# 2_cyber60-smk_matrix.net
KiCad netlist of a schematic drawn in Altium Designer
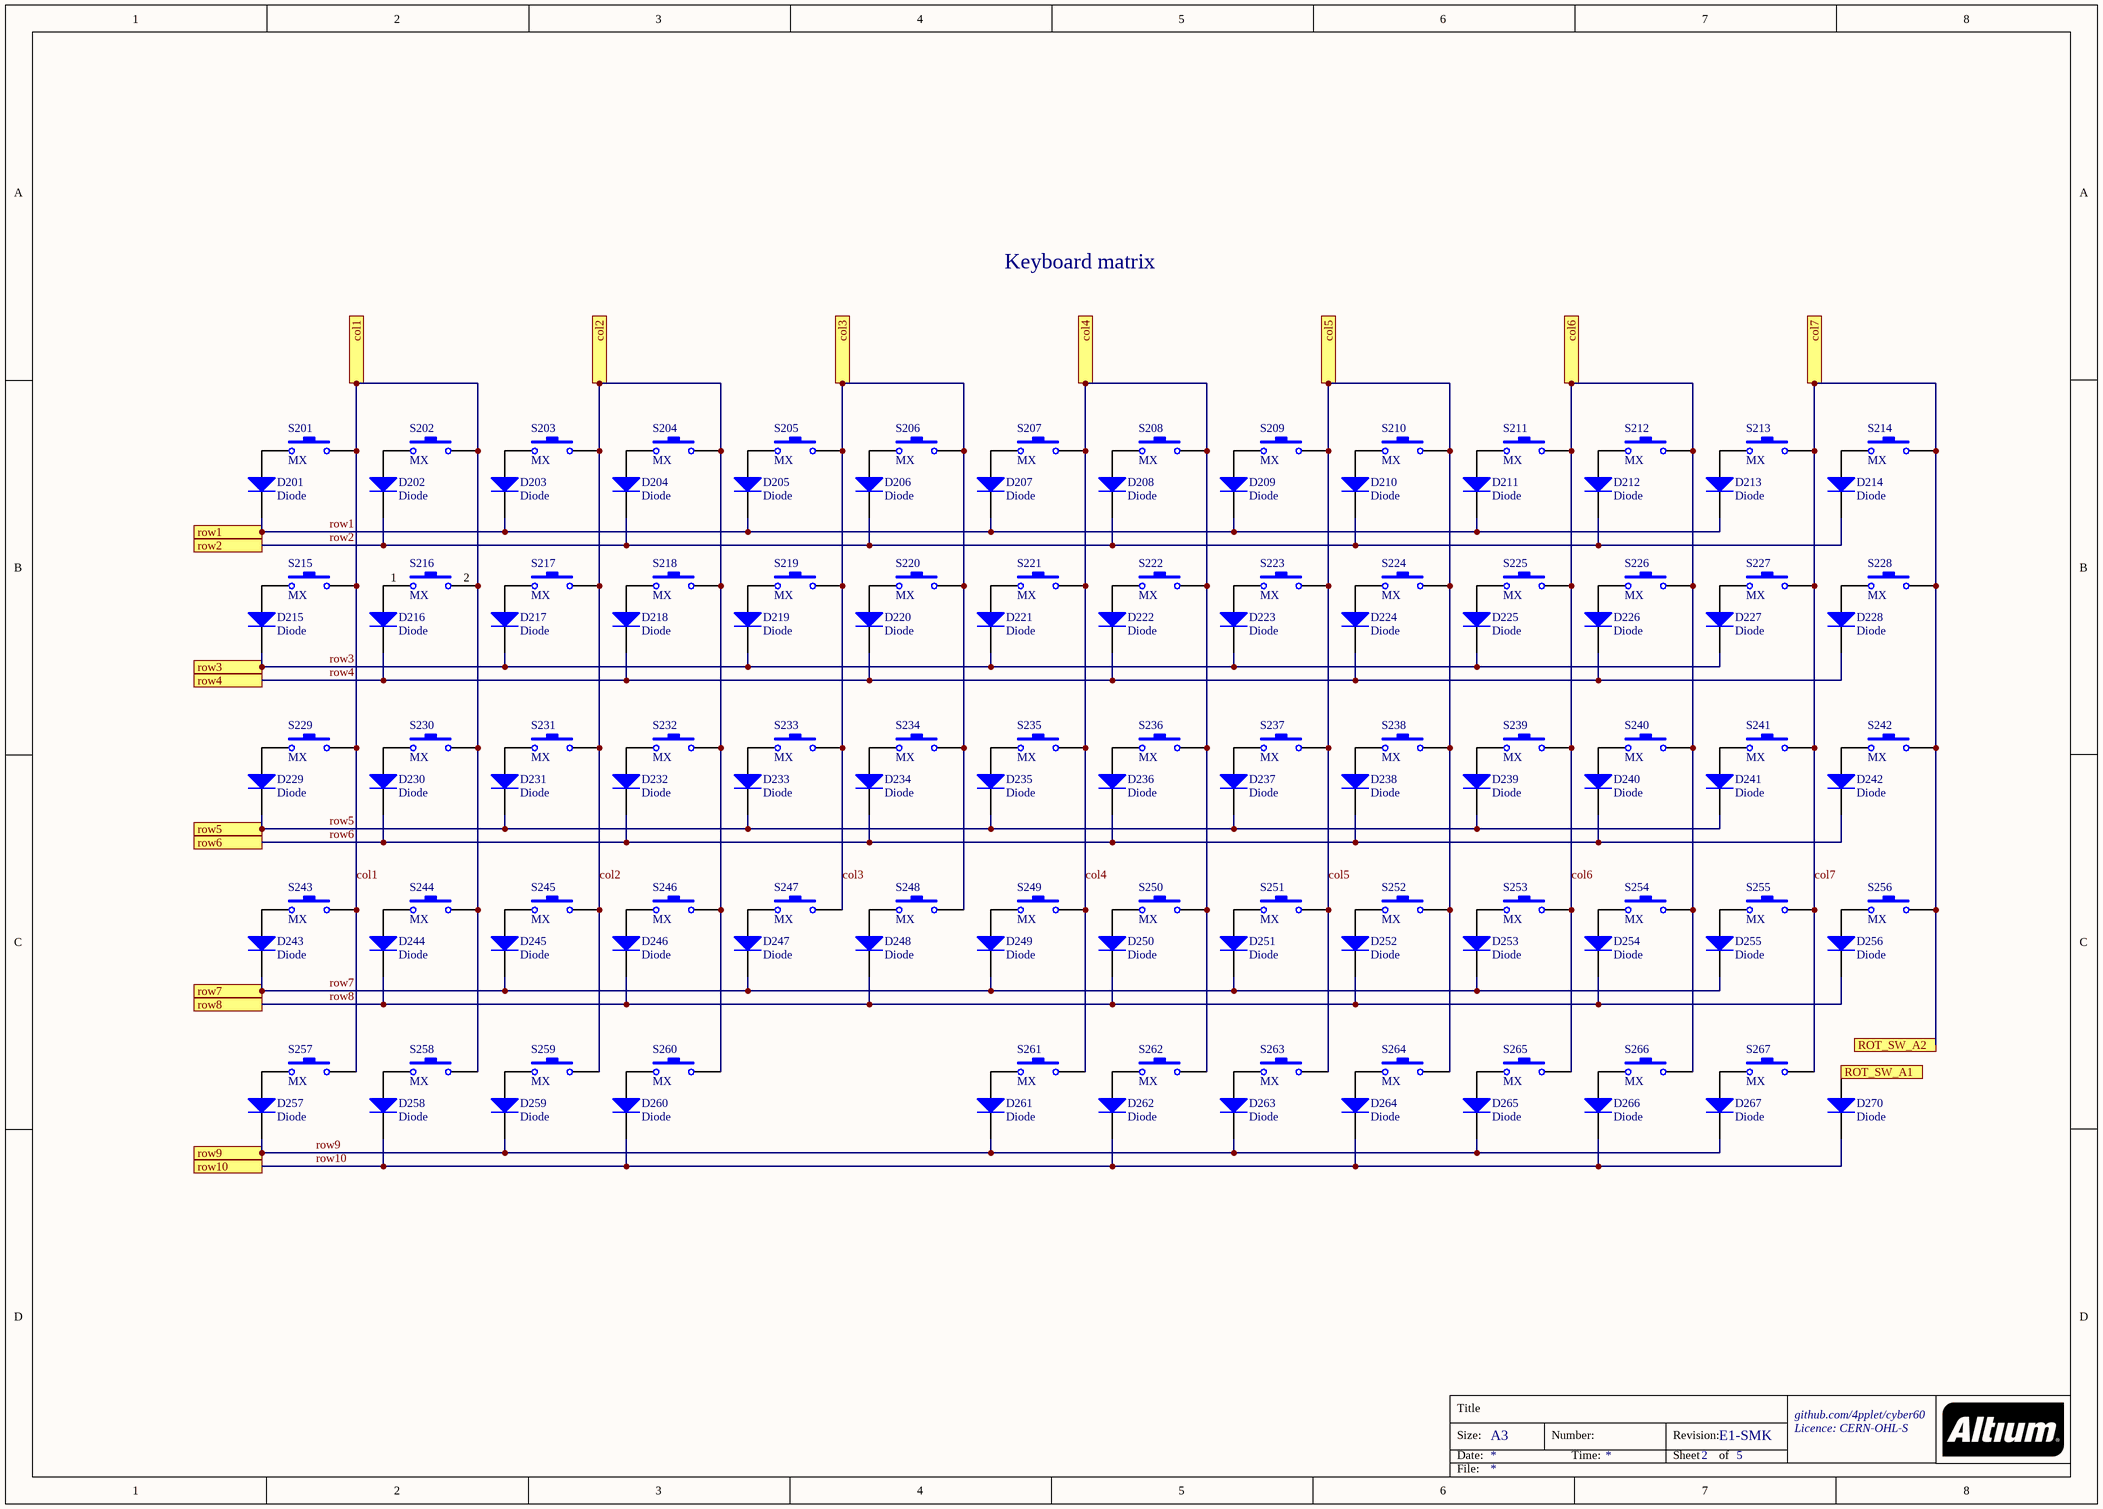
[diagram p0: 2_cyber60-smk_matrix.SchDoc]

(export (version "E")
  (design (tool "Eeschema 10.0.6"))
  (components
    (comp (ref "D201")
      (value "Diode")
      (footprint "SOD-123")
      (description "Default Diode")
      (fields (field (name "LCSC PART #") "C81598") (field (name "MRF.PART") "1N4148W"))
      (libsource (lib "Miscellaneous Devices") (part "Diode"))
    )
    (comp (ref "D202")
      (value "Diode")
      (footprint "SOD-123")
      (description "Default Diode")
      (fields (field (name "LCSC PART #") "C81598") (field (name "MRF.PART") "1N4148W"))
      (libsource (lib "Miscellaneous Devices") (part "Diode"))
    )
    (comp (ref "D203")
      (value "Diode")
      (footprint "SOD-123")
      (description "Default Diode")
      (fields (field (name "LCSC PART #") "C81598") (field (name "MRF.PART") "1N4148W"))
      (libsource (lib "Miscellaneous Devices") (part "Diode"))
    )
    (comp (ref "D204")
      (value "Diode")
      (footprint "SOD-123")
      (description "Default Diode")
      (fields (field (name "LCSC PART #") "C81598") (field (name "MRF.PART") "1N4148W"))
      (libsource (lib "Miscellaneous Devices") (part "Diode"))
    )
    (comp (ref "D205")
      (value "Diode")
      (footprint "SOD-123")
      (description "Default Diode")
      (fields (field (name "LCSC PART #") "C81598") (field (name "MRF.PART") "1N4148W"))
      (libsource (lib "Miscellaneous Devices") (part "Diode"))
    )
    (comp (ref "D206")
      (value "Diode")
      (footprint "SOD-123")
      (description "Default Diode")
      (fields (field (name "LCSC PART #") "C81598") (field (name "MRF.PART") "1N4148W"))
      (libsource (lib "Miscellaneous Devices") (part "Diode"))
    )
    (comp (ref "D207")
      (value "Diode")
      (footprint "SOD-123")
      (description "Default Diode")
      (fields (field (name "LCSC PART #") "C81598") (field (name "MRF.PART") "1N4148W"))
      (libsource (lib "Miscellaneous Devices") (part "Diode"))
    )
    (comp (ref "D208")
      (value "Diode")
      (footprint "SOD-123")
      (description "Default Diode")
      (fields (field (name "LCSC PART #") "C81598") (field (name "MRF.PART") "1N4148W"))
      (libsource (lib "Miscellaneous Devices") (part "Diode"))
    )
    (comp (ref "D209")
      (value "Diode")
      (footprint "SOD-123")
      (description "Default Diode")
      (fields (field (name "LCSC PART #") "C81598") (field (name "MRF.PART") "1N4148W"))
      (libsource (lib "Miscellaneous Devices") (part "Diode"))
    )
    (comp (ref "D210")
      (value "Diode")
      (footprint "SOD-123")
      (description "Default Diode")
      (fields (field (name "LCSC PART #") "C81598") (field (name "MRF.PART") "1N4148W"))
      (libsource (lib "Miscellaneous Devices") (part "Diode"))
    )
    (comp (ref "D211")
      (value "Diode")
      (footprint "SOD-123")
      (description "Default Diode")
      (fields (field (name "LCSC PART #") "C81598") (field (name "MRF.PART") "1N4148W"))
      (libsource (lib "Miscellaneous Devices") (part "Diode"))
    )
    (comp (ref "D212")
      (value "Diode")
      (footprint "SOD-123")
      (description "Default Diode")
      (fields (field (name "LCSC PART #") "C81598") (field (name "MRF.PART") "1N4148W"))
      (libsource (lib "Miscellaneous Devices") (part "Diode"))
    )
    (comp (ref "D213")
      (value "Diode")
      (footprint "SOD-123")
      (description "Default Diode")
      (fields (field (name "LCSC PART #") "C81598") (field (name "MRF.PART") "1N4148W"))
      (libsource (lib "Miscellaneous Devices") (part "Diode"))
    )
    (comp (ref "D214")
      (value "Diode")
      (footprint "SOD-123")
      (description "Default Diode")
      (fields (field (name "LCSC PART #") "C81598") (field (name "MRF.PART") "1N4148W"))
      (libsource (lib "Miscellaneous Devices") (part "Diode"))
    )
    (comp (ref "D215")
      (value "Diode")
      (footprint "SOD-123")
      (description "Default Diode")
      (fields (field (name "LCSC PART #") "C81598") (field (name "MRF.PART") "1N4148W"))
      (libsource (lib "Miscellaneous Devices") (part "Diode"))
    )
    (comp (ref "D216")
      (value "Diode")
      (footprint "SOD-123")
      (description "Default Diode")
      (fields (field (name "LCSC PART #") "C81598") (field (name "MRF.PART") "1N4148W"))
      (libsource (lib "Miscellaneous Devices") (part "Diode"))
    )
    (comp (ref "D217")
      (value "Diode")
      (footprint "SOD-123")
      (description "Default Diode")
      (fields (field (name "LCSC PART #") "C81598") (field (name "MRF.PART") "1N4148W"))
      (libsource (lib "Miscellaneous Devices") (part "Diode"))
    )
    (comp (ref "D218")
      (value "Diode")
      (footprint "SOD-123")
      (description "Default Diode")
      (fields (field (name "LCSC PART #") "C81598") (field (name "MRF.PART") "1N4148W"))
      (libsource (lib "Miscellaneous Devices") (part "Diode"))
    )
    (comp (ref "D219")
      (value "Diode")
      (footprint "SOD-123")
      (description "Default Diode")
      (fields (field (name "LCSC PART #") "C81598") (field (name "MRF.PART") "1N4148W"))
      (libsource (lib "Miscellaneous Devices") (part "Diode"))
    )
    (comp (ref "D220")
      (value "Diode")
      (footprint "SOD-123")
      (description "Default Diode")
      (fields (field (name "LCSC PART #") "C81598") (field (name "MRF.PART") "1N4148W"))
      (libsource (lib "Miscellaneous Devices") (part "Diode"))
    )
    (comp (ref "D221")
      (value "Diode")
      (footprint "SOD-123")
      (description "Default Diode")
      (fields (field (name "LCSC PART #") "C81598") (field (name "MRF.PART") "1N4148W"))
      (libsource (lib "Miscellaneous Devices") (part "Diode"))
    )
    (comp (ref "D222")
      (value "Diode")
      (footprint "SOD-123")
      (description "Default Diode")
      (fields (field (name "LCSC PART #") "C81598") (field (name "MRF.PART") "1N4148W"))
      (libsource (lib "Miscellaneous Devices") (part "Diode"))
    )
    (comp (ref "D223")
      (value "Diode")
      (footprint "SOD-123")
      (description "Default Diode")
      (fields (field (name "LCSC PART #") "C81598") (field (name "MRF.PART") "1N4148W"))
      (libsource (lib "Miscellaneous Devices") (part "Diode"))
    )
    (comp (ref "D224")
      (value "Diode")
      (footprint "SOD-123")
      (description "Default Diode")
      (fields (field (name "LCSC PART #") "C81598") (field (name "MRF.PART") "1N4148W"))
      (libsource (lib "Miscellaneous Devices") (part "Diode"))
    )
    (comp (ref "D225")
      (value "Diode")
      (footprint "SOD-123")
      (description "Default Diode")
      (fields (field (name "LCSC PART #") "C81598") (field (name "MRF.PART") "1N4148W"))
      (libsource (lib "Miscellaneous Devices") (part "Diode"))
    )
    (comp (ref "D226")
      (value "Diode")
      (footprint "SOD-123")
      (description "Default Diode")
      (fields (field (name "LCSC PART #") "C81598") (field (name "MRF.PART") "1N4148W"))
      (libsource (lib "Miscellaneous Devices") (part "Diode"))
    )
    (comp (ref "D227")
      (value "Diode")
      (footprint "SOD-123")
      (description "Default Diode")
      (fields (field (name "LCSC PART #") "C81598") (field (name "MRF.PART") "1N4148W"))
      (libsource (lib "Miscellaneous Devices") (part "Diode"))
    )
    (comp (ref "D228")
      (value "Diode")
      (footprint "SOD-123")
      (description "Default Diode")
      (fields (field (name "LCSC PART #") "C81598") (field (name "MRF.PART") "1N4148W"))
      (libsource (lib "Miscellaneous Devices") (part "Diode"))
    )
    (comp (ref "D229")
      (value "Diode")
      (footprint "SOD-123")
      (description "Default Diode")
      (fields (field (name "LCSC PART #") "C81598") (field (name "MRF.PART") "1N4148W"))
      (libsource (lib "Miscellaneous Devices") (part "Diode"))
    )
    (comp (ref "D230")
      (value "Diode")
      (footprint "SOD-123")
      (description "Default Diode")
      (fields (field (name "LCSC PART #") "C81598") (field (name "MRF.PART") "1N4148W"))
      (libsource (lib "Miscellaneous Devices") (part "Diode"))
    )
    (comp (ref "D231")
      (value "Diode")
      (footprint "SOD-123")
      (description "Default Diode")
      (fields (field (name "LCSC PART #") "C81598") (field (name "MRF.PART") "1N4148W"))
      (libsource (lib "Miscellaneous Devices") (part "Diode"))
    )
    (comp (ref "D232")
      (value "Diode")
      (footprint "SOD-123")
      (description "Default Diode")
      (fields (field (name "LCSC PART #") "C81598") (field (name "MRF.PART") "1N4148W"))
      (libsource (lib "Miscellaneous Devices") (part "Diode"))
    )
    (comp (ref "D233")
      (value "Diode")
      (footprint "SOD-123")
      (description "Default Diode")
      (fields (field (name "LCSC PART #") "C81598") (field (name "MRF.PART") "1N4148W"))
      (libsource (lib "Miscellaneous Devices") (part "Diode"))
    )
    (comp (ref "D234")
      (value "Diode")
      (footprint "SOD-123")
      (description "Default Diode")
      (fields (field (name "LCSC PART #") "C81598") (field (name "MRF.PART") "1N4148W"))
      (libsource (lib "Miscellaneous Devices") (part "Diode"))
    )
    (comp (ref "D235")
      (value "Diode")
      (footprint "SOD-123")
      (description "Default Diode")
      (fields (field (name "LCSC PART #") "C81598") (field (name "MRF.PART") "1N4148W"))
      (libsource (lib "Miscellaneous Devices") (part "Diode"))
    )
    (comp (ref "D236")
      (value "Diode")
      (footprint "SOD-123")
      (description "Default Diode")
      (fields (field (name "LCSC PART #") "C81598") (field (name "MRF.PART") "1N4148W"))
      (libsource (lib "Miscellaneous Devices") (part "Diode"))
    )
    (comp (ref "D237")
      (value "Diode")
      (footprint "SOD-123")
      (description "Default Diode")
      (fields (field (name "LCSC PART #") "C81598") (field (name "MRF.PART") "1N4148W"))
      (libsource (lib "Miscellaneous Devices") (part "Diode"))
    )
    (comp (ref "D238")
      (value "Diode")
      (footprint "SOD-123")
      (description "Default Diode")
      (fields (field (name "LCSC PART #") "C81598") (field (name "MRF.PART") "1N4148W"))
      (libsource (lib "Miscellaneous Devices") (part "Diode"))
    )
    (comp (ref "D239")
      (value "Diode")
      (footprint "SOD-123")
      (description "Default Diode")
      (fields (field (name "LCSC PART #") "C81598") (field (name "MRF.PART") "1N4148W"))
      (libsource (lib "Miscellaneous Devices") (part "Diode"))
    )
    (comp (ref "D240")
      (value "Diode")
      (footprint "SOD-123")
      (description "Default Diode")
      (fields (field (name "LCSC PART #") "C81598") (field (name "MRF.PART") "1N4148W"))
      (libsource (lib "Miscellaneous Devices") (part "Diode"))
    )
    (comp (ref "D241")
      (value "Diode")
      (footprint "SOD-123")
      (description "Default Diode")
      (fields (field (name "LCSC PART #") "C81598") (field (name "MRF.PART") "1N4148W"))
      (libsource (lib "Miscellaneous Devices") (part "Diode"))
    )
    (comp (ref "D242")
      (value "Diode")
      (footprint "SOD-123")
      (description "Default Diode")
      (fields (field (name "LCSC PART #") "C81598") (field (name "MRF.PART") "1N4148W"))
      (libsource (lib "Miscellaneous Devices") (part "Diode"))
    )
    (comp (ref "D243")
      (value "Diode")
      (footprint "SOD-123")
      (description "Default Diode")
      (fields (field (name "LCSC PART #") "C81598") (field (name "MRF.PART") "1N4148W"))
      (libsource (lib "Miscellaneous Devices") (part "Diode"))
    )
    (comp (ref "D244")
      (value "Diode")
      (footprint "SOD-123")
      (description "Default Diode")
      (fields (field (name "LCSC PART #") "C81598") (field (name "MRF.PART") "1N4148W"))
      (libsource (lib "Miscellaneous Devices") (part "Diode"))
    )
    (comp (ref "D245")
      (value "Diode")
      (footprint "SOD-123")
      (description "Default Diode")
      (fields (field (name "LCSC PART #") "C81598") (field (name "MRF.PART") "1N4148W"))
      (libsource (lib "Miscellaneous Devices") (part "Diode"))
    )
    (comp (ref "D246")
      (value "Diode")
      (footprint "SOD-123")
      (description "Default Diode")
      (fields (field (name "LCSC PART #") "C81598") (field (name "MRF.PART") "1N4148W"))
      (libsource (lib "Miscellaneous Devices") (part "Diode"))
    )
    (comp (ref "D247")
      (value "Diode")
      (footprint "SOD-123")
      (description "Default Diode")
      (fields (field (name "LCSC PART #") "C81598") (field (name "MRF.PART") "1N4148W"))
      (libsource (lib "Miscellaneous Devices") (part "Diode"))
    )
    (comp (ref "D248")
      (value "Diode")
      (footprint "SOD-123")
      (description "Default Diode")
      (fields (field (name "LCSC PART #") "C81598") (field (name "MRF.PART") "1N4148W"))
      (libsource (lib "Miscellaneous Devices") (part "Diode"))
    )
    (comp (ref "D249")
      (value "Diode")
      (footprint "SOD-123")
      (description "Default Diode")
      (fields (field (name "LCSC PART #") "C81598") (field (name "MRF.PART") "1N4148W"))
      (libsource (lib "Miscellaneous Devices") (part "Diode"))
    )
    (comp (ref "D250")
      (value "Diode")
      (footprint "SOD-123")
      (description "Default Diode")
      (fields (field (name "LCSC PART #") "C81598") (field (name "MRF.PART") "1N4148W"))
      (libsource (lib "Miscellaneous Devices") (part "Diode"))
    )
    (comp (ref "D251")
      (value "Diode")
      (footprint "SOD-123")
      (description "Default Diode")
      (fields (field (name "LCSC PART #") "C81598") (field (name "MRF.PART") "1N4148W"))
      (libsource (lib "Miscellaneous Devices") (part "Diode"))
    )
    (comp (ref "D252")
      (value "Diode")
      (footprint "SOD-123")
      (description "Default Diode")
      (fields (field (name "LCSC PART #") "C81598") (field (name "MRF.PART") "1N4148W"))
      (libsource (lib "Miscellaneous Devices") (part "Diode"))
    )
    (comp (ref "D253")
      (value "Diode")
      (footprint "SOD-123")
      (description "Default Diode")
      (fields (field (name "LCSC PART #") "C81598") (field (name "MRF.PART") "1N4148W"))
      (libsource (lib "Miscellaneous Devices") (part "Diode"))
    )
    (comp (ref "D254")
      (value "Diode")
      (footprint "SOD-123")
      (description "Default Diode")
      (fields (field (name "LCSC PART #") "C81598") (field (name "MRF.PART") "1N4148W"))
      (libsource (lib "Miscellaneous Devices") (part "Diode"))
    )
    (comp (ref "D255")
      (value "Diode")
      (footprint "SOD-123")
      (description "Default Diode")
      (fields (field (name "LCSC PART #") "C81598") (field (name "MRF.PART") "1N4148W"))
      (libsource (lib "Miscellaneous Devices") (part "Diode"))
    )
    (comp (ref "D256")
      (value "Diode")
      (footprint "SOD-123")
      (description "Default Diode")
      (fields (field (name "LCSC PART #") "C81598") (field (name "MRF.PART") "1N4148W"))
      (libsource (lib "Miscellaneous Devices") (part "Diode"))
    )
    (comp (ref "D257")
      (value "Diode")
      (footprint "SOD-123")
      (description "Default Diode")
      (fields (field (name "LCSC PART #") "C81598") (field (name "MRF.PART") "1N4148W"))
      (libsource (lib "Miscellaneous Devices") (part "Diode"))
    )
    (comp (ref "D258")
      (value "Diode")
      (footprint "SOD-123")
      (description "Default Diode")
      (fields (field (name "LCSC PART #") "C81598") (field (name "MRF.PART") "1N4148W"))
      (libsource (lib "Miscellaneous Devices") (part "Diode"))
    )
    (comp (ref "D259")
      (value "Diode")
      (footprint "SOD-123")
      (description "Default Diode")
      (fields (field (name "LCSC PART #") "C81598") (field (name "MRF.PART") "1N4148W"))
      (libsource (lib "Miscellaneous Devices") (part "Diode"))
    )
    (comp (ref "D260")
      (value "Diode")
      (footprint "SOD-123")
      (description "Default Diode")
      (fields (field (name "LCSC PART #") "C81598") (field (name "MRF.PART") "1N4148W"))
      (libsource (lib "Miscellaneous Devices") (part "Diode"))
    )
    (comp (ref "D261")
      (value "Diode")
      (footprint "SOD-123")
      (description "Default Diode")
      (fields (field (name "LCSC PART #") "C81598") (field (name "MRF.PART") "1N4148W"))
      (libsource (lib "Miscellaneous Devices") (part "Diode"))
    )
    (comp (ref "D262")
      (value "Diode")
      (footprint "SOD-123")
      (description "Default Diode")
      (fields (field (name "LCSC PART #") "C81598") (field (name "MRF.PART") "1N4148W"))
      (libsource (lib "Miscellaneous Devices") (part "Diode"))
    )
    (comp (ref "D263")
      (value "Diode")
      (footprint "SOD-123")
      (description "Default Diode")
      (fields (field (name "LCSC PART #") "C81598") (field (name "MRF.PART") "1N4148W"))
      (libsource (lib "Miscellaneous Devices") (part "Diode"))
    )
    (comp (ref "D264")
      (value "Diode")
      (footprint "SOD-123")
      (description "Default Diode")
      (fields (field (name "LCSC PART #") "C81598") (field (name "MRF.PART") "1N4148W"))
      (libsource (lib "Miscellaneous Devices") (part "Diode"))
    )
    (comp (ref "D265")
      (value "Diode")
      (footprint "SOD-123")
      (description "Default Diode")
      (fields (field (name "LCSC PART #") "C81598") (field (name "MRF.PART") "1N4148W"))
      (libsource (lib "Miscellaneous Devices") (part "Diode"))
    )
    (comp (ref "D266")
      (value "Diode")
      (footprint "SOD-123")
      (description "Default Diode")
      (fields (field (name "LCSC PART #") "C81598") (field (name "MRF.PART") "1N4148W"))
      (libsource (lib "Miscellaneous Devices") (part "Diode"))
    )
    (comp (ref "D267")
      (value "Diode")
      (footprint "SOD-123")
      (description "Default Diode")
      (fields (field (name "LCSC PART #") "C81598") (field (name "MRF.PART") "1N4148W"))
      (libsource (lib "Miscellaneous Devices") (part "Diode"))
    )
    (comp (ref "D270")
      (value "Diode")
      (footprint "SOD-123")
      (description "Default Diode")
      (fields (field (name "LCSC PART #") "C81598") (field (name "MRF.PART") "1N4148W"))
      (libsource (lib "Miscellaneous Devices") (part "Diode"))
    )
    (comp (ref "S201")
      (value "MX")
      (footprint "SMK-switch")
      (description "Switch")
      (libsource (lib "Miscellaneous Devices") (part "SW-PB"))
    )
    (comp (ref "S202")
      (value "MX")
      (footprint "SMK-switch - switched polarity")
      (description "Switch")
      (libsource (lib "Miscellaneous Devices") (part "SW-PB"))
    )
    (comp (ref "S203")
      (value "MX")
      (footprint "SMK-switch - switched polarity")
      (description "Switch")
      (libsource (lib "Miscellaneous Devices") (part "SW-PB"))
    )
    (comp (ref "S204")
      (value "MX")
      (footprint "SMK-switch")
      (description "Switch")
      (libsource (lib "Miscellaneous Devices") (part "SW-PB"))
    )
    (comp (ref "S205")
      (value "MX")
      (footprint "SMK-switch - switched polarity")
      (description "Switch")
      (libsource (lib "Miscellaneous Devices") (part "SW-PB"))
    )
    (comp (ref "S206")
      (value "MX")
      (footprint "SMK-switch - switched polarity")
      (description "Switch")
      (libsource (lib "Miscellaneous Devices") (part "SW-PB"))
    )
    (comp (ref "S207")
      (value "MX")
      (footprint "SMK-switch - switched polarity")
      (description "Switch")
      (libsource (lib "Miscellaneous Devices") (part "SW-PB"))
    )
    (comp (ref "S208")
      (value "MX")
      (footprint "SMK-switch - switched polarity")
      (description "Switch")
      (libsource (lib "Miscellaneous Devices") (part "SW-PB"))
    )
    (comp (ref "S209")
      (value "MX")
      (footprint "SMK-switch - switched polarity")
      (description "Switch")
      (libsource (lib "Miscellaneous Devices") (part "SW-PB"))
    )
    (comp (ref "S210")
      (value "MX")
      (footprint "SMK-switch - switched polarity")
      (description "Switch")
      (libsource (lib "Miscellaneous Devices") (part "SW-PB"))
    )
    (comp (ref "S211")
      (value "MX")
      (footprint "SMK-switch - switched polarity")
      (description "Switch")
      (libsource (lib "Miscellaneous Devices") (part "SW-PB"))
    )
    (comp (ref "S212")
      (value "MX")
      (footprint "SMK-switch - switched polarity")
      (description "Switch")
      (libsource (lib "Miscellaneous Devices") (part "SW-PB"))
    )
    (comp (ref "S213")
      (value "MX")
      (footprint "SMK-switch - switched polarity")
      (description "Switch")
      (libsource (lib "Miscellaneous Devices") (part "SW-PB"))
    )
    (comp (ref "S214")
      (value "MX")
      (footprint "SMK-switch - switched polarity")
      (description "Switch")
      (libsource (lib "Miscellaneous Devices") (part "SW-PB"))
    )
    (comp (ref "S215")
      (value "MX")
      (footprint "SMK-switch - switched polarity")
      (description "TAB")
      (libsource (lib "Miscellaneous Devices") (part "SW-PB"))
    )
    (comp (ref "S216")
      (value "MX")
      (footprint "SMK-switch - switched polarity")
      (description "Switch")
      (libsource (lib "") (part "SW-PB_1"))
    )
    (comp (ref "S217")
      (value "MX")
      (footprint "SMK-switch - switched polarity")
      (description "Switch")
      (libsource (lib "Miscellaneous Devices") (part "SW-PB"))
    )
    (comp (ref "S218")
      (value "MX")
      (footprint "SMK-switch - switched polarity")
      (description "Switch")
      (libsource (lib "Miscellaneous Devices") (part "SW-PB"))
    )
    (comp (ref "S219")
      (value "MX")
      (footprint "SMK-switch - switched polarity")
      (description "Switch")
      (libsource (lib "Miscellaneous Devices") (part "SW-PB"))
    )
    (comp (ref "S220")
      (value "MX")
      (footprint "SMK-switch")
      (description "Switch")
      (libsource (lib "Miscellaneous Devices") (part "SW-PB"))
    )
    (comp (ref "S221")
      (value "MX")
      (footprint "SMK-switch - switched polarity")
      (description "Switch")
      (libsource (lib "Miscellaneous Devices") (part "SW-PB"))
    )
    (comp (ref "S222")
      (value "MX")
      (footprint "SMK-switch - switched polarity")
      (description "Switch")
      (libsource (lib "Miscellaneous Devices") (part "SW-PB"))
    )
    (comp (ref "S223")
      (value "MX")
      (footprint "SMK-switch - switched polarity")
      (description "Switch")
      (libsource (lib "Miscellaneous Devices") (part "SW-PB"))
    )
    (comp (ref "S224")
      (value "MX")
      (footprint "SMK-switch - switched polarity")
      (description "Switch")
      (libsource (lib "Miscellaneous Devices") (part "SW-PB"))
    )
    (comp (ref "S225")
      (value "MX")
      (footprint "SMK-switch - switched polarity")
      (description "Switch")
      (libsource (lib "Miscellaneous Devices") (part "SW-PB"))
    )
    (comp (ref "S226")
      (value "MX")
      (footprint "SMK-switch")
      (description "Switch")
      (libsource (lib "Miscellaneous Devices") (part "SW-PB"))
    )
    (comp (ref "S227")
      (value "MX")
      (footprint "SMK-switch")
      (description "Switch")
      (libsource (lib "Miscellaneous Devices") (part "SW-PB"))
    )
    (comp (ref "S228")
      (value "MX")
      (footprint "SMK-switch - backspace")
      (description "Switch")
      (libsource (lib "Miscellaneous Devices") (part "SW-PB"))
    )
    (comp (ref "S229")
      (value "MX")
      (footprint "SMK-switch - CAPS")
      (description "Switch")
      (libsource (lib "Miscellaneous Devices") (part "SW-PB"))
    )
    (comp (ref "S230")
      (value "MX")
      (footprint "SMK-switch - switched polarity")
      (description "Switch")
      (libsource (lib "Miscellaneous Devices") (part "SW-PB"))
    )
    (comp (ref "S231")
      (value "MX")
      (footprint "SMK-switch - switched polarity")
      (description "Switch")
      (libsource (lib "Miscellaneous Devices") (part "SW-PB"))
    )
    (comp (ref "S232")
      (value "MX")
      (footprint "SMK-switch - switched polarity")
      (description "Switch")
      (libsource (lib "Miscellaneous Devices") (part "SW-PB"))
    )
    (comp (ref "S233")
      (value "MX")
      (footprint "SMK-switch - switched polarity")
      (description "Switch")
      (libsource (lib "Miscellaneous Devices") (part "SW-PB"))
    )
    (comp (ref "S234")
      (value "MX")
      (footprint "SMK-switch")
      (description "Switch")
      (libsource (lib "Miscellaneous Devices") (part "SW-PB"))
    )
    (comp (ref "S235")
      (value "MX")
      (footprint "SMK-switch - switched polarity")
      (description "Switch")
      (libsource (lib "Miscellaneous Devices") (part "SW-PB"))
    )
    (comp (ref "S236")
      (value "MX")
      (footprint "SMK-switch - switched polarity")
      (description "Switch")
      (libsource (lib "Miscellaneous Devices") (part "SW-PB"))
    )
    (comp (ref "S237")
      (value "MX")
      (footprint "SMK-switch - switched polarity")
      (description "Switch")
      (libsource (lib "Miscellaneous Devices") (part "SW-PB"))
    )
    (comp (ref "S238")
      (value "MX")
      (footprint "SMK-switch - switched polarity")
      (description "Switch")
      (libsource (lib "Miscellaneous Devices") (part "SW-PB"))
    )
    (comp (ref "S239")
      (value "MX")
      (footprint "SMK-switch")
      (description "Switch")
      (libsource (lib "Miscellaneous Devices") (part "SW-PB"))
    )
    (comp (ref "S240")
      (value "MX")
      (footprint "SMK-switch - switched polarity")
      (description "Switch")
      (libsource (lib "Miscellaneous Devices") (part "SW-PB"))
    )
    (comp (ref "S241")
      (value "MX")
      (footprint "SMK-switch")
      (description "Switch")
      (libsource (lib "Miscellaneous Devices") (part "SW-PB"))
    )
    (comp (ref "S242")
      (value "MX")
      (footprint "SMK-switch - 1.5U")
      (description "Switch")
      (libsource (lib "Miscellaneous Devices") (part "SW-PB"))
    )
    (comp (ref "S243")
      (value "MX")
      (footprint "SMK-switch - Left shift v2")
      (description "Switch")
      (libsource (lib "Miscellaneous Devices") (part "SW-PB"))
    )
    (comp (ref "S244")
      (value "MX")
      (footprint "SMK-switch - switched polarity")
      (description "Switch")
      (libsource (lib "Miscellaneous Devices") (part "SW-PB"))
    )
    (comp (ref "S245")
      (value "MX")
      (footprint "SMK-switch - switched polarity")
      (description "Switch")
      (libsource (lib "Miscellaneous Devices") (part "SW-PB"))
    )
    (comp (ref "S246")
      (value "MX")
      (footprint "SMK-switch - switched polarity")
      (description "Switch")
      (libsource (lib "Miscellaneous Devices") (part "SW-PB"))
    )
    (comp (ref "S247")
      (value "MX")
      (footprint "SMK-switch - switched polarity")
      (description "Switch")
      (libsource (lib "Miscellaneous Devices") (part "SW-PB"))
    )
    (comp (ref "S248")
      (value "MX")
      (footprint "SMK-switch")
      (description "Switch")
      (libsource (lib "Miscellaneous Devices") (part "SW-PB"))
    )
    (comp (ref "S249")
      (value "MX")
      (footprint "SMK-switch - switched polarity")
      (description "Switch")
      (libsource (lib "Miscellaneous Devices") (part "SW-PB"))
    )
    (comp (ref "S250")
      (value "MX")
      (footprint "SMK-switch")
      (description "Switch")
      (libsource (lib "Miscellaneous Devices") (part "SW-PB"))
    )
    (comp (ref "S251")
      (value "MX")
      (footprint "SMK-switch - switched polarity")
      (description "Switch")
      (libsource (lib "Miscellaneous Devices") (part "SW-PB"))
    )
    (comp (ref "S252")
      (value "MX")
      (footprint "SMK-switch - switched polarity")
      (description "Switch")
      (libsource (lib "Miscellaneous Devices") (part "SW-PB"))
    )
    (comp (ref "S253")
      (value "MX")
      (footprint "SMK-switch - switched polarity")
      (description "Switch")
      (libsource (lib "Miscellaneous Devices") (part "SW-PB"))
    )
    (comp (ref "S254")
      (value "MX")
      (footprint "SMK-switch - switched polarity")
      (description "Switch")
      (libsource (lib "Miscellaneous Devices") (part "SW-PB"))
    )
    (comp (ref "S255")
      (value "MX")
      (footprint "SMK-switch")
      (description "Switch")
      (libsource (lib "Miscellaneous Devices") (part "SW-PB"))
    )
    (comp (ref "S256")
      (value "MX")
      (footprint "SMK-switch - Enter - rotated stab")
      (description "Switch")
      (libsource (lib "Miscellaneous Devices") (part "SW-PB"))
    )
    (comp (ref "S257")
      (value "MX")
      (footprint "SMK-switch - 1.5u MOD-L")
      (description "Switch")
      (libsource (lib "Miscellaneous Devices") (part "SW-PB"))
    )
    (comp (ref "S258")
      (value "MX")
      (footprint "SMK-switch - L_WIN V2")
      (description "Switch")
      (libsource (lib "Miscellaneous Devices") (part "SW-PB"))
    )
    (comp (ref "S259")
      (value "MX")
      (footprint "SMK-switch - L_ALT V2")
      (description "Switch")
      (libsource (lib "Miscellaneous Devices") (part "SW-PB"))
    )
    (comp (ref "S260")
      (value "MX")
      (footprint "SMK-switch - 2.75U - rotated stab")
      (description "Switch")
      (libsource (lib "Miscellaneous Devices") (part "SW-PB"))
    )
    (comp (ref "S261")
      (value "MX")
      (footprint "SMK-switch - Space_V2")
      (description "Switch")
      (libsource (lib "Miscellaneous Devices") (part "SW-PB"))
    )
    (comp (ref "S262")
      (value "MX")
      (footprint "SMK-switch - 2.75U - rotated stab")
      (description "Switch")
      (libsource (lib "Miscellaneous Devices") (part "SW-PB"))
    )
    (comp (ref "S263")
      (value "MX")
      (footprint "SMK-switch - switched polarity")
      (description "Switch")
      (libsource (lib "Miscellaneous Devices") (part "SW-PB"))
    )
    (comp (ref "S264")
      (value "MX")
      (footprint "SMK-switch - R_ALT V2")
      (description "Switch")
      (libsource (lib "Miscellaneous Devices") (part "SW-PB"))
    )
    (comp (ref "S265")
      (value "MX")
      (footprint "SMK-switch - R_WIN V2")
      (description "Switch")
      (libsource (lib "Miscellaneous Devices") (part "SW-PB"))
    )
    (comp (ref "S266")
      (value "MX")
      (footprint "SMK-switch - 1.5u MOD-R")
      (description "Switch")
      (libsource (lib "Miscellaneous Devices") (part "SW-PB"))
    )
    (comp (ref "S267")
      (value "MX")
      (footprint "SMK-switch - right shift v2")
      (description "Switch")
      (libsource (lib "Miscellaneous Devices") (part "SW-PB"))
    )
  )
  (nets
    (net (code "1") (name "/ROT_SW_A1") (class "Default")
      (node (ref "D270") (pin "1") (pinfunction "A_1") (pintype "passive"))
    )
    (net (code "2") (name "/col1") (class "Default")
      (node (ref "S201") (pin "2") (pinfunction "2_2") (pintype "passive"))
      (node (ref "S202") (pin "2") (pinfunction "2_2") (pintype "passive"))
      (node (ref "S215") (pin "2") (pinfunction "2_2") (pintype "passive"))
      (node (ref "S216") (pin "2") (pinfunction "2_2") (pintype "passive"))
      (node (ref "S229") (pin "2") (pinfunction "2_2") (pintype "passive"))
      (node (ref "S230") (pin "2") (pinfunction "2_2") (pintype "passive"))
      (node (ref "S243") (pin "2") (pinfunction "2_2") (pintype "passive"))
      (node (ref "S244") (pin "2") (pinfunction "2_2") (pintype "passive"))
      (node (ref "S257") (pin "2") (pinfunction "2_2") (pintype "passive"))
      (node (ref "S258") (pin "2") (pinfunction "2_2") (pintype "passive"))
    )
    (net (code "3") (name "/col2") (class "Default")
      (node (ref "S203") (pin "2") (pinfunction "2_2") (pintype "passive"))
      (node (ref "S204") (pin "2") (pinfunction "2_2") (pintype "passive"))
      (node (ref "S217") (pin "2") (pinfunction "2_2") (pintype "passive"))
      (node (ref "S218") (pin "2") (pinfunction "2_2") (pintype "passive"))
      (node (ref "S231") (pin "2") (pinfunction "2_2") (pintype "passive"))
      (node (ref "S232") (pin "2") (pinfunction "2_2") (pintype "passive"))
      (node (ref "S245") (pin "2") (pinfunction "2_2") (pintype "passive"))
      (node (ref "S246") (pin "2") (pinfunction "2_2") (pintype "passive"))
      (node (ref "S259") (pin "2") (pinfunction "2_2") (pintype "passive"))
      (node (ref "S260") (pin "2") (pinfunction "2_2") (pintype "passive"))
    )
    (net (code "4") (name "/col3") (class "Default")
      (node (ref "S205") (pin "2") (pinfunction "2_2") (pintype "passive"))
      (node (ref "S206") (pin "2") (pinfunction "2_2") (pintype "passive"))
      (node (ref "S219") (pin "2") (pinfunction "2_2") (pintype "passive"))
      (node (ref "S220") (pin "2") (pinfunction "2_2") (pintype "passive"))
      (node (ref "S233") (pin "2") (pinfunction "2_2") (pintype "passive"))
      (node (ref "S234") (pin "2") (pinfunction "2_2") (pintype "passive"))
      (node (ref "S247") (pin "2") (pinfunction "2_2") (pintype "passive"))
      (node (ref "S248") (pin "2") (pinfunction "2_2") (pintype "passive"))
    )
    (net (code "5") (name "/col4") (class "Default")
      (node (ref "S207") (pin "2") (pinfunction "2_2") (pintype "passive"))
      (node (ref "S208") (pin "2") (pinfunction "2_2") (pintype "passive"))
      (node (ref "S221") (pin "2") (pinfunction "2_2") (pintype "passive"))
      (node (ref "S222") (pin "2") (pinfunction "2_2") (pintype "passive"))
      (node (ref "S235") (pin "2") (pinfunction "2_2") (pintype "passive"))
      (node (ref "S236") (pin "2") (pinfunction "2_2") (pintype "passive"))
      (node (ref "S249") (pin "2") (pinfunction "2_2") (pintype "passive"))
      (node (ref "S250") (pin "2") (pinfunction "2_2") (pintype "passive"))
      (node (ref "S261") (pin "1") (pinfunction "1_1") (pintype "passive"))
      (node (ref "S262") (pin "2") (pinfunction "2_2") (pintype "passive"))
    )
    (net (code "6") (name "/col5") (class "Default")
      (node (ref "S209") (pin "2") (pinfunction "2_2") (pintype "passive"))
      (node (ref "S210") (pin "2") (pinfunction "2_2") (pintype "passive"))
      (node (ref "S223") (pin "2") (pinfunction "2_2") (pintype "passive"))
      (node (ref "S224") (pin "2") (pinfunction "2_2") (pintype "passive"))
      (node (ref "S237") (pin "2") (pinfunction "2_2") (pintype "passive"))
      (node (ref "S238") (pin "2") (pinfunction "2_2") (pintype "passive"))
      (node (ref "S251") (pin "2") (pinfunction "2_2") (pintype "passive"))
      (node (ref "S252") (pin "2") (pinfunction "2_2") (pintype "passive"))
      (node (ref "S263") (pin "2") (pinfunction "2_2") (pintype "passive"))
      (node (ref "S264") (pin "1") (pinfunction "1_1") (pintype "passive"))
    )
    (net (code "7") (name "/col6") (class "Default")
      (node (ref "S211") (pin "2") (pinfunction "2_2") (pintype "passive"))
      (node (ref "S212") (pin "2") (pinfunction "2_2") (pintype "passive"))
      (node (ref "S225") (pin "2") (pinfunction "2_2") (pintype "passive"))
      (node (ref "S226") (pin "2") (pinfunction "2_2") (pintype "passive"))
      (node (ref "S239") (pin "2") (pinfunction "2_2") (pintype "passive"))
      (node (ref "S240") (pin "2") (pinfunction "2_2") (pintype "passive"))
      (node (ref "S253") (pin "2") (pinfunction "2_2") (pintype "passive"))
      (node (ref "S254") (pin "2") (pinfunction "2_2") (pintype "passive"))
      (node (ref "S265") (pin "2") (pinfunction "2_2") (pintype "passive"))
      (node (ref "S266") (pin "2") (pinfunction "2_2") (pintype "passive"))
    )
    (net (code "8") (name "/col7") (class "Default")
      (node (ref "S213") (pin "2") (pinfunction "2_2") (pintype "passive"))
      (node (ref "S214") (pin "2") (pinfunction "2_2") (pintype "passive"))
      (node (ref "S227") (pin "2") (pinfunction "2_2") (pintype "passive"))
      (node (ref "S228") (pin "1") (pinfunction "1_1") (pintype "passive"))
      (node (ref "S241") (pin "2") (pinfunction "2_2") (pintype "passive"))
      (node (ref "S242") (pin "2") (pinfunction "2_2") (pintype "passive"))
      (node (ref "S255") (pin "2") (pinfunction "2_2") (pintype "passive"))
      (node (ref "S256") (pin "2") (pinfunction "2_2") (pintype "passive"))
      (node (ref "S267") (pin "2") (pinfunction "2_2") (pintype "passive"))
    )
    (net (code "9") (name "/row1") (class "Default")
      (node (ref "D201") (pin "2") (pinfunction "K_2") (pintype "passive"))
      (node (ref "D203") (pin "2") (pinfunction "K_2") (pintype "passive"))
      (node (ref "D205") (pin "2") (pinfunction "K_2") (pintype "passive"))
      (node (ref "D207") (pin "2") (pinfunction "K_2") (pintype "passive"))
      (node (ref "D209") (pin "2") (pinfunction "K_2") (pintype "passive"))
      (node (ref "D211") (pin "2") (pinfunction "K_2") (pintype "passive"))
      (node (ref "D213") (pin "2") (pinfunction "K_2") (pintype "passive"))
    )
    (net (code "10") (name "/row2") (class "Default")
      (node (ref "D202") (pin "2") (pinfunction "K_2") (pintype "passive"))
      (node (ref "D204") (pin "2") (pinfunction "K_2") (pintype "passive"))
      (node (ref "D206") (pin "2") (pinfunction "K_2") (pintype "passive"))
      (node (ref "D208") (pin "2") (pinfunction "K_2") (pintype "passive"))
      (node (ref "D210") (pin "2") (pinfunction "K_2") (pintype "passive"))
      (node (ref "D212") (pin "2") (pinfunction "K_2") (pintype "passive"))
      (node (ref "D214") (pin "2") (pinfunction "K_2") (pintype "passive"))
    )
    (net (code "11") (name "/row3") (class "Default")
      (node (ref "D215") (pin "2") (pinfunction "K_2") (pintype "passive"))
      (node (ref "D217") (pin "2") (pinfunction "K_2") (pintype "passive"))
      (node (ref "D219") (pin "2") (pinfunction "K_2") (pintype "passive"))
      (node (ref "D221") (pin "2") (pinfunction "K_2") (pintype "passive"))
      (node (ref "D223") (pin "2") (pinfunction "K_2") (pintype "passive"))
      (node (ref "D225") (pin "2") (pinfunction "K_2") (pintype "passive"))
      (node (ref "D227") (pin "2") (pinfunction "K_2") (pintype "passive"))
    )
    (net (code "12") (name "/row4") (class "Default")
      (node (ref "D216") (pin "2") (pinfunction "K_2") (pintype "passive"))
      (node (ref "D218") (pin "2") (pinfunction "K_2") (pintype "passive"))
      (node (ref "D220") (pin "2") (pinfunction "K_2") (pintype "passive"))
      (node (ref "D222") (pin "2") (pinfunction "K_2") (pintype "passive"))
      (node (ref "D224") (pin "2") (pinfunction "K_2") (pintype "passive"))
      (node (ref "D226") (pin "2") (pinfunction "K_2") (pintype "passive"))
      (node (ref "D228") (pin "2") (pinfunction "K_2") (pintype "passive"))
    )
    (net (code "13") (name "/row5") (class "Default")
      (node (ref "D229") (pin "2") (pinfunction "K_2") (pintype "passive"))
      (node (ref "D231") (pin "2") (pinfunction "K_2") (pintype "passive"))
      (node (ref "D233") (pin "2") (pinfunction "K_2") (pintype "passive"))
      (node (ref "D235") (pin "2") (pinfunction "K_2") (pintype "passive"))
      (node (ref "D237") (pin "2") (pinfunction "K_2") (pintype "passive"))
      (node (ref "D239") (pin "2") (pinfunction "K_2") (pintype "passive"))
      (node (ref "D241") (pin "2") (pinfunction "K_2") (pintype "passive"))
    )
    (net (code "14") (name "/row6") (class "Default")
      (node (ref "D230") (pin "2") (pinfunction "K_2") (pintype "passive"))
      (node (ref "D232") (pin "2") (pinfunction "K_2") (pintype "passive"))
      (node (ref "D234") (pin "2") (pinfunction "K_2") (pintype "passive"))
      (node (ref "D236") (pin "2") (pinfunction "K_2") (pintype "passive"))
      (node (ref "D238") (pin "2") (pinfunction "K_2") (pintype "passive"))
      (node (ref "D240") (pin "2") (pinfunction "K_2") (pintype "passive"))
      (node (ref "D242") (pin "2") (pinfunction "K_2") (pintype "passive"))
    )
    (net (code "15") (name "/row7") (class "Default")
      (node (ref "D243") (pin "2") (pinfunction "K_2") (pintype "passive"))
      (node (ref "D245") (pin "2") (pinfunction "K_2") (pintype "passive"))
      (node (ref "D247") (pin "2") (pinfunction "K_2") (pintype "passive"))
      (node (ref "D249") (pin "2") (pinfunction "K_2") (pintype "passive"))
      (node (ref "D251") (pin "2") (pinfunction "K_2") (pintype "passive"))
      (node (ref "D253") (pin "2") (pinfunction "K_2") (pintype "passive"))
      (node (ref "D255") (pin "2") (pinfunction "K_2") (pintype "passive"))
    )
    (net (code "16") (name "/row8") (class "Default")
      (node (ref "D244") (pin "2") (pinfunction "K_2") (pintype "passive"))
      (node (ref "D246") (pin "2") (pinfunction "K_2") (pintype "passive"))
      (node (ref "D248") (pin "2") (pinfunction "K_2") (pintype "passive"))
      (node (ref "D250") (pin "2") (pinfunction "K_2") (pintype "passive"))
      (node (ref "D252") (pin "2") (pinfunction "K_2") (pintype "passive"))
      (node (ref "D254") (pin "2") (pinfunction "K_2") (pintype "passive"))
      (node (ref "D256") (pin "2") (pinfunction "K_2") (pintype "passive"))
    )
    (net (code "17") (name "/row9") (class "Default")
      (node (ref "D257") (pin "2") (pinfunction "K_2") (pintype "passive"))
      (node (ref "D259") (pin "2") (pinfunction "K_2") (pintype "passive"))
      (node (ref "D261") (pin "2") (pinfunction "K_2") (pintype "passive"))
      (node (ref "D263") (pin "2") (pinfunction "K_2") (pintype "passive"))
      (node (ref "D265") (pin "2") (pinfunction "K_2") (pintype "passive"))
      (node (ref "D267") (pin "2") (pinfunction "K_2") (pintype "passive"))
    )
    (net (code "18") (name "/row10") (class "Default")
      (node (ref "D258") (pin "2") (pinfunction "K_2") (pintype "passive"))
      (node (ref "D260") (pin "2") (pinfunction "K_2") (pintype "passive"))
      (node (ref "D262") (pin "2") (pinfunction "K_2") (pintype "passive"))
      (node (ref "D264") (pin "2") (pinfunction "K_2") (pintype "passive"))
      (node (ref "D266") (pin "2") (pinfunction "K_2") (pintype "passive"))
      (node (ref "D270") (pin "2") (pinfunction "K_2") (pintype "passive"))
    )
    (net (code "19") (name "Net-(D201-A)") (class "Default")
      (node (ref "D201") (pin "1") (pinfunction "A_1") (pintype "passive"))
      (node (ref "S201") (pin "1") (pinfunction "1_1") (pintype "passive"))
    )
    (net (code "20") (name "Net-(D202-A)") (class "Default")
      (node (ref "D202") (pin "1") (pinfunction "A_1") (pintype "passive"))
      (node (ref "S202") (pin "1") (pinfunction "1_1") (pintype "passive"))
    )
    (net (code "21") (name "Net-(D203-A)") (class "Default")
      (node (ref "D203") (pin "1") (pinfunction "A_1") (pintype "passive"))
      (node (ref "S203") (pin "1") (pinfunction "1_1") (pintype "passive"))
    )
    (net (code "22") (name "Net-(D204-A)") (class "Default")
      (node (ref "D204") (pin "1") (pinfunction "A_1") (pintype "passive"))
      (node (ref "S204") (pin "1") (pinfunction "1_1") (pintype "passive"))
    )
    (net (code "23") (name "Net-(D205-A)") (class "Default")
      (node (ref "D205") (pin "1") (pinfunction "A_1") (pintype "passive"))
      (node (ref "S205") (pin "1") (pinfunction "1_1") (pintype "passive"))
    )
    (net (code "24") (name "Net-(D206-A)") (class "Default")
      (node (ref "D206") (pin "1") (pinfunction "A_1") (pintype "passive"))
      (node (ref "S206") (pin "1") (pinfunction "1_1") (pintype "passive"))
    )
    (net (code "25") (name "Net-(D207-A)") (class "Default")
      (node (ref "D207") (pin "1") (pinfunction "A_1") (pintype "passive"))
      (node (ref "S207") (pin "1") (pinfunction "1_1") (pintype "passive"))
    )
    (net (code "26") (name "Net-(D208-A)") (class "Default")
      (node (ref "D208") (pin "1") (pinfunction "A_1") (pintype "passive"))
      (node (ref "S208") (pin "1") (pinfunction "1_1") (pintype "passive"))
    )
    (net (code "27") (name "Net-(D209-A)") (class "Default")
      (node (ref "D209") (pin "1") (pinfunction "A_1") (pintype "passive"))
      (node (ref "S209") (pin "1") (pinfunction "1_1") (pintype "passive"))
    )
    (net (code "28") (name "Net-(D210-A)") (class "Default")
      (node (ref "D210") (pin "1") (pinfunction "A_1") (pintype "passive"))
      (node (ref "S210") (pin "1") (pinfunction "1_1") (pintype "passive"))
    )
    (net (code "29") (name "Net-(D211-A)") (class "Default")
      (node (ref "D211") (pin "1") (pinfunction "A_1") (pintype "passive"))
      (node (ref "S211") (pin "1") (pinfunction "1_1") (pintype "passive"))
    )
    (net (code "30") (name "Net-(D212-A)") (class "Default")
      (node (ref "D212") (pin "1") (pinfunction "A_1") (pintype "passive"))
      (node (ref "S212") (pin "1") (pinfunction "1_1") (pintype "passive"))
    )
    (net (code "31") (name "Net-(D213-A)") (class "Default")
      (node (ref "D213") (pin "1") (pinfunction "A_1") (pintype "passive"))
      (node (ref "S213") (pin "1") (pinfunction "1_1") (pintype "passive"))
    )
    (net (code "32") (name "Net-(D214-A)") (class "Default")
      (node (ref "D214") (pin "1") (pinfunction "A_1") (pintype "passive"))
      (node (ref "S214") (pin "1") (pinfunction "1_1") (pintype "passive"))
    )
    (net (code "33") (name "Net-(D215-A)") (class "Default")
      (node (ref "D215") (pin "1") (pinfunction "A_1") (pintype "passive"))
      (node (ref "S215") (pin "1") (pinfunction "1_1") (pintype "passive"))
    )
    (net (code "34") (name "Net-(D216-A)") (class "Default")
      (node (ref "D216") (pin "1") (pinfunction "A_1") (pintype "passive"))
      (node (ref "S216") (pin "1") (pinfunction "1_1") (pintype "passive"))
    )
    (net (code "35") (name "Net-(D217-A)") (class "Default")
      (node (ref "D217") (pin "1") (pinfunction "A_1") (pintype "passive"))
      (node (ref "S217") (pin "1") (pinfunction "1_1") (pintype "passive"))
    )
    (net (code "36") (name "Net-(D218-A)") (class "Default")
      (node (ref "D218") (pin "1") (pinfunction "A_1") (pintype "passive"))
      (node (ref "S218") (pin "1") (pinfunction "1_1") (pintype "passive"))
    )
    (net (code "37") (name "Net-(D219-A)") (class "Default")
      (node (ref "D219") (pin "1") (pinfunction "A_1") (pintype "passive"))
      (node (ref "S219") (pin "1") (pinfunction "1_1") (pintype "passive"))
    )
    (net (code "38") (name "Net-(D220-A)") (class "Default")
      (node (ref "D220") (pin "1") (pinfunction "A_1") (pintype "passive"))
      (node (ref "S220") (pin "1") (pinfunction "1_1") (pintype "passive"))
    )
    (net (code "39") (name "Net-(D221-A)") (class "Default")
      (node (ref "D221") (pin "1") (pinfunction "A_1") (pintype "passive"))
      (node (ref "S221") (pin "1") (pinfunction "1_1") (pintype "passive"))
    )
    (net (code "40") (name "Net-(D222-A)") (class "Default")
      (node (ref "D222") (pin "1") (pinfunction "A_1") (pintype "passive"))
      (node (ref "S222") (pin "1") (pinfunction "1_1") (pintype "passive"))
    )
    (net (code "41") (name "Net-(D223-A)") (class "Default")
      (node (ref "D223") (pin "1") (pinfunction "A_1") (pintype "passive"))
      (node (ref "S223") (pin "1") (pinfunction "1_1") (pintype "passive"))
    )
    (net (code "42") (name "Net-(D224-A)") (class "Default")
      (node (ref "D224") (pin "1") (pinfunction "A_1") (pintype "passive"))
      (node (ref "S224") (pin "1") (pinfunction "1_1") (pintype "passive"))
    )
    (net (code "43") (name "Net-(D225-A)") (class "Default")
      (node (ref "D225") (pin "1") (pinfunction "A_1") (pintype "passive"))
      (node (ref "S225") (pin "1") (pinfunction "1_1") (pintype "passive"))
    )
    (net (code "44") (name "Net-(D226-A)") (class "Default")
      (node (ref "D226") (pin "1") (pinfunction "A_1") (pintype "passive"))
      (node (ref "S226") (pin "1") (pinfunction "1_1") (pintype "passive"))
    )
    (net (code "45") (name "Net-(D227-A)") (class "Default")
      (node (ref "D227") (pin "1") (pinfunction "A_1") (pintype "passive"))
      (node (ref "S227") (pin "1") (pinfunction "1_1") (pintype "passive"))
    )
    (net (code "46") (name "Net-(D228-A)") (class "Default")
      (node (ref "D228") (pin "1") (pinfunction "A_1") (pintype "passive"))
      (node (ref "S228") (pin "2") (pinfunction "2_2") (pintype "passive"))
    )
    (net (code "47") (name "Net-(D229-A)") (class "Default")
      (node (ref "D229") (pin "1") (pinfunction "A_1") (pintype "passive"))
      (node (ref "S229") (pin "1") (pinfunction "1_1") (pintype "passive"))
    )
    (net (code "48") (name "Net-(D230-A)") (class "Default")
      (node (ref "D230") (pin "1") (pinfunction "A_1") (pintype "passive"))
      (node (ref "S230") (pin "1") (pinfunction "1_1") (pintype "passive"))
    )
    (net (code "49") (name "Net-(D231-A)") (class "Default")
      (node (ref "D231") (pin "1") (pinfunction "A_1") (pintype "passive"))
      (node (ref "S231") (pin "1") (pinfunction "1_1") (pintype "passive"))
    )
    (net (code "50") (name "Net-(D232-A)") (class "Default")
      (node (ref "D232") (pin "1") (pinfunction "A_1") (pintype "passive"))
      (node (ref "S232") (pin "1") (pinfunction "1_1") (pintype "passive"))
    )
    (net (code "51") (name "Net-(D233-A)") (class "Default")
      (node (ref "D233") (pin "1") (pinfunction "A_1") (pintype "passive"))
      (node (ref "S233") (pin "1") (pinfunction "1_1") (pintype "passive"))
    )
    (net (code "52") (name "Net-(D234-A)") (class "Default")
      (node (ref "D234") (pin "1") (pinfunction "A_1") (pintype "passive"))
      (node (ref "S234") (pin "1") (pinfunction "1_1") (pintype "passive"))
    )
    (net (code "53") (name "Net-(D235-A)") (class "Default")
      (node (ref "D235") (pin "1") (pinfunction "A_1") (pintype "passive"))
      (node (ref "S235") (pin "1") (pinfunction "1_1") (pintype "passive"))
    )
    (net (code "54") (name "Net-(D236-A)") (class "Default")
      (node (ref "D236") (pin "1") (pinfunction "A_1") (pintype "passive"))
      (node (ref "S236") (pin "1") (pinfunction "1_1") (pintype "passive"))
    )
    (net (code "55") (name "Net-(D237-A)") (class "Default")
      (node (ref "D237") (pin "1") (pinfunction "A_1") (pintype "passive"))
      (node (ref "S237") (pin "1") (pinfunction "1_1") (pintype "passive"))
    )
    (net (code "56") (name "Net-(D238-A)") (class "Default")
      (node (ref "D238") (pin "1") (pinfunction "A_1") (pintype "passive"))
      (node (ref "S238") (pin "1") (pinfunction "1_1") (pintype "passive"))
    )
    (net (code "57") (name "Net-(D239-A)") (class "Default")
      (node (ref "D239") (pin "1") (pinfunction "A_1") (pintype "passive"))
      (node (ref "S239") (pin "1") (pinfunction "1_1") (pintype "passive"))
    )
    (net (code "58") (name "Net-(D240-A)") (class "Default")
      (node (ref "D240") (pin "1") (pinfunction "A_1") (pintype "passive"))
      (node (ref "S240") (pin "1") (pinfunction "1_1") (pintype "passive"))
    )
    (net (code "59") (name "Net-(D241-A)") (class "Default")
      (node (ref "D241") (pin "1") (pinfunction "A_1") (pintype "passive"))
      (node (ref "S241") (pin "1") (pinfunction "1_1") (pintype "passive"))
    )
    (net (code "60") (name "Net-(D242-A)") (class "Default")
      (node (ref "D242") (pin "1") (pinfunction "A_1") (pintype "passive"))
      (node (ref "S242") (pin "1") (pinfunction "1_1") (pintype "passive"))
    )
    (net (code "61") (name "Net-(D243-A)") (class "Default")
      (node (ref "D243") (pin "1") (pinfunction "A_1") (pintype "passive"))
      (node (ref "S243") (pin "1") (pinfunction "1_1") (pintype "passive"))
    )
    (net (code "62") (name "Net-(D244-A)") (class "Default")
      (node (ref "D244") (pin "1") (pinfunction "A_1") (pintype "passive"))
      (node (ref "S244") (pin "1") (pinfunction "1_1") (pintype "passive"))
    )
    (net (code "63") (name "Net-(D245-A)") (class "Default")
      (node (ref "D245") (pin "1") (pinfunction "A_1") (pintype "passive"))
      (node (ref "S245") (pin "1") (pinfunction "1_1") (pintype "passive"))
    )
    (net (code "64") (name "Net-(D246-A)") (class "Default")
      (node (ref "D246") (pin "1") (pinfunction "A_1") (pintype "passive"))
      (node (ref "S246") (pin "1") (pinfunction "1_1") (pintype "passive"))
    )
    (net (code "65") (name "Net-(D247-A)") (class "Default")
      (node (ref "D247") (pin "1") (pinfunction "A_1") (pintype "passive"))
      (node (ref "S247") (pin "1") (pinfunction "1_1") (pintype "passive"))
    )
    (net (code "66") (name "Net-(D248-A)") (class "Default")
      (node (ref "D248") (pin "1") (pinfunction "A_1") (pintype "passive"))
      (node (ref "S248") (pin "1") (pinfunction "1_1") (pintype "passive"))
    )
    (net (code "67") (name "Net-(D249-A)") (class "Default")
      (node (ref "D249") (pin "1") (pinfunction "A_1") (pintype "passive"))
      (node (ref "S249") (pin "1") (pinfunction "1_1") (pintype "passive"))
    )
    (net (code "68") (name "Net-(D250-A)") (class "Default")
      (node (ref "D250") (pin "1") (pinfunction "A_1") (pintype "passive"))
      (node (ref "S250") (pin "1") (pinfunction "1_1") (pintype "passive"))
    )
    (net (code "69") (name "Net-(D251-A)") (class "Default")
      (node (ref "D251") (pin "1") (pinfunction "A_1") (pintype "passive"))
      (node (ref "S251") (pin "1") (pinfunction "1_1") (pintype "passive"))
    )
    (net (code "70") (name "Net-(D252-A)") (class "Default")
      (node (ref "D252") (pin "1") (pinfunction "A_1") (pintype "passive"))
      (node (ref "S252") (pin "1") (pinfunction "1_1") (pintype "passive"))
    )
    (net (code "71") (name "Net-(D253-A)") (class "Default")
      (node (ref "D253") (pin "1") (pinfunction "A_1") (pintype "passive"))
      (node (ref "S253") (pin "1") (pinfunction "1_1") (pintype "passive"))
    )
    (net (code "72") (name "Net-(D254-A)") (class "Default")
      (node (ref "D254") (pin "1") (pinfunction "A_1") (pintype "passive"))
      (node (ref "S254") (pin "1") (pinfunction "1_1") (pintype "passive"))
    )
    (net (code "73") (name "Net-(D255-A)") (class "Default")
      (node (ref "D255") (pin "1") (pinfunction "A_1") (pintype "passive"))
      (node (ref "S255") (pin "1") (pinfunction "1_1") (pintype "passive"))
    )
    (net (code "74") (name "Net-(D256-A)") (class "Default")
      (node (ref "D256") (pin "1") (pinfunction "A_1") (pintype "passive"))
      (node (ref "S256") (pin "1") (pinfunction "1_1") (pintype "passive"))
    )
    (net (code "75") (name "Net-(D257-A)") (class "Default")
      (node (ref "D257") (pin "1") (pinfunction "A_1") (pintype "passive"))
      (node (ref "S257") (pin "1") (pinfunction "1_1") (pintype "passive"))
    )
    (net (code "76") (name "Net-(D258-A)") (class "Default")
      (node (ref "D258") (pin "1") (pinfunction "A_1") (pintype "passive"))
      (node (ref "S258") (pin "1") (pinfunction "1_1") (pintype "passive"))
    )
    (net (code "77") (name "Net-(D259-A)") (class "Default")
      (node (ref "D259") (pin "1") (pinfunction "A_1") (pintype "passive"))
      (node (ref "S259") (pin "1") (pinfunction "1_1") (pintype "passive"))
    )
    (net (code "78") (name "Net-(D260-A)") (class "Default")
      (node (ref "D260") (pin "1") (pinfunction "A_1") (pintype "passive"))
      (node (ref "S260") (pin "1") (pinfunction "1_1") (pintype "passive"))
    )
    (net (code "79") (name "Net-(D261-A)") (class "Default")
      (node (ref "D261") (pin "1") (pinfunction "A_1") (pintype "passive"))
      (node (ref "S261") (pin "2") (pinfunction "2_2") (pintype "passive"))
    )
    (net (code "80") (name "Net-(D262-A)") (class "Default")
      (node (ref "D262") (pin "1") (pinfunction "A_1") (pintype "passive"))
      (node (ref "S262") (pin "1") (pinfunction "1_1") (pintype "passive"))
    )
    (net (code "81") (name "Net-(D263-A)") (class "Default")
      (node (ref "D263") (pin "1") (pinfunction "A_1") (pintype "passive"))
      (node (ref "S263") (pin "1") (pinfunction "1_1") (pintype "passive"))
    )
    (net (code "82") (name "Net-(D264-A)") (class "Default")
      (node (ref "D264") (pin "1") (pinfunction "A_1") (pintype "passive"))
      (node (ref "S264") (pin "2") (pinfunction "2_2") (pintype "passive"))
    )
    (net (code "83") (name "Net-(D265-A)") (class "Default")
      (node (ref "D265") (pin "1") (pinfunction "A_1") (pintype "passive"))
      (node (ref "S265") (pin "1") (pinfunction "1_1") (pintype "passive"))
    )
    (net (code "84") (name "Net-(D266-A)") (class "Default")
      (node (ref "D266") (pin "1") (pinfunction "A_1") (pintype "passive"))
      (node (ref "S266") (pin "1") (pinfunction "1_1") (pintype "passive"))
    )
    (net (code "85") (name "Net-(D267-A)") (class "Default")
      (node (ref "D267") (pin "1") (pinfunction "A_1") (pintype "passive"))
      (node (ref "S267") (pin "1") (pinfunction "1_1") (pintype "passive"))
    )
  )
)
